# Encoder.net
KiCad netlist of a schematic drawn in Altium Designer
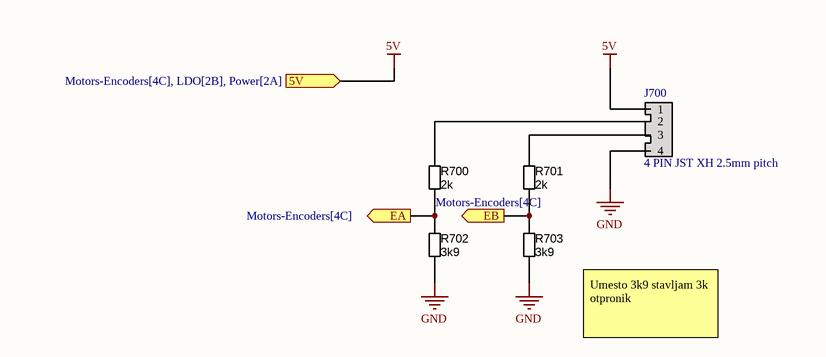
[diagram p0: Encoder.SchDoc]

(export (version "E")
  (design (tool "Eeschema 10.0.6"))
  (components
    (comp (ref "J700")
      (value "4 PIN JST XH 2.5mm pitch")
      (footprint "Connectors:JST4PIN")
      (libsource (lib "Connectors") (part "JST4PIN"))
    )
    (comp (ref "R700")
      (value "2k")
      (footprint "RES_0603")
      (description "RES 2k OHM 1% 1/10W 0603")
      (libsource (lib "ResistorsIntegrated") (part "R000004"))
    )
    (comp (ref "R701")
      (value "2k")
      (footprint "RES_0603")
      (description "RES 2k OHM 1% 1/10W 0603")
      (libsource (lib "ResistorsIntegrated") (part "R000004"))
    )
    (comp (ref "R702")
      (value "3k9")
      (footprint "RES_0603")
      (description "RES 3k9 OHM 1% 1/10W 0603")
      (libsource (lib "ResistorsIntegrated") (part "R000004"))
    )
    (comp (ref "R703")
      (value "3k9")
      (footprint "RES_0603")
      (description "RES 3k9 OHM 1% 1/10W 0603")
      (libsource (lib "ResistorsIntegrated") (part "R000004"))
    )
  )
  (nets
    (net (code "1") (name "/EA") (class "Default")
      (node (ref "R700") (pin "1") (pinfunction "1_1") (pintype "passive"))
      (node (ref "R702") (pin "2") (pinfunction "2_2") (pintype "passive"))
    )
    (net (code "2") (name "/EB") (class "Default")
      (node (ref "R701") (pin "1") (pinfunction "1_1") (pintype "passive"))
      (node (ref "R703") (pin "2") (pinfunction "2_2") (pintype "passive"))
    )
    (net (code "3") (name "5V") (class "Default")
      (node (ref "J700") (pin "1") (pinfunction "1_1") (pintype "passive"))
    )
    (net (code "4") (name "GND") (class "Default")
      (node (ref "J700") (pin "4") (pinfunction "4_4") (pintype "passive"))
      (node (ref "R702") (pin "1") (pinfunction "1_1") (pintype "passive"))
      (node (ref "R703") (pin "1") (pinfunction "1_1") (pintype "passive"))
    )
    (net (code "5") (name "Net-(J700-Pad2)") (class "Default")
      (node (ref "J700") (pin "2") (pinfunction "2_2") (pintype "passive"))
      (node (ref "R700") (pin "2") (pinfunction "2_2") (pintype "passive"))
    )
    (net (code "6") (name "Net-(J700-Pad3)") (class "Default")
      (node (ref "J700") (pin "3") (pinfunction "3_3") (pintype "passive"))
      (node (ref "R701") (pin "2") (pinfunction "2_2") (pintype "passive"))
    )
  )
)
